# feedline.net
KiCad netlist of a schematic drawn in EAGLE
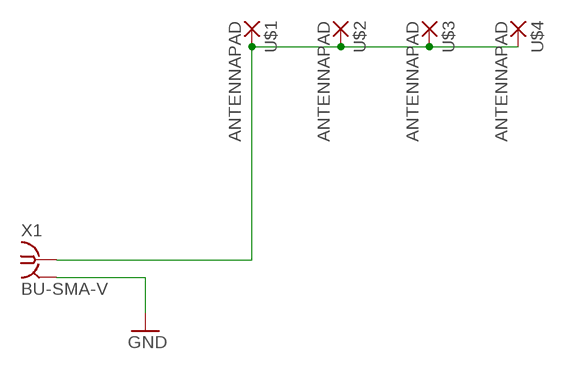
[diagram p0: schematic, sheet 1]

(export (version "E")
  (design (tool "Eeschema 10.0.6"))
  (components
    (comp (ref "U$1")
      (value "ANTENNAPAD")
      (footprint "eagle-import:CMMOUNTPAD")
      (libsource (lib "eagle-import") (part "ANTENNAPAD"))
    )
    (comp (ref "U$2")
      (value "ANTENNAPAD")
      (footprint "eagle-import:CMMOUNTPAD")
      (libsource (lib "eagle-import") (part "ANTENNAPAD"))
    )
    (comp (ref "U$3")
      (value "ANTENNAPAD")
      (footprint "eagle-import:CMMOUNTPAD")
      (libsource (lib "eagle-import") (part "ANTENNAPAD"))
    )
    (comp (ref "U$4")
      (value "ANTENNAPAD")
      (footprint "eagle-import:CMMOUNTPAD")
      (libsource (lib "eagle-import") (part "ANTENNAPAD"))
    )
    (comp (ref "X1")
      (value "BU-SMA-V")
      (footprint "eagle-import:BU-SMA-V")
      (libsource (lib "eagle-import") (part "BU-SMA-V"))
    )
  )
  (nets
    (net (code "1") (name "GND") (class "Default")
      (node (ref "X1") (pin "2") (pinfunction "2_2") (pintype "passive"))
      (node (ref "X1") (pin "3") (pinfunction "2_3") (pintype "passive"))
      (node (ref "X1") (pin "4") (pinfunction "2_4") (pintype "passive"))
      (node (ref "X1") (pin "5") (pinfunction "2_5") (pintype "passive"))
    )
    (net (code "2") (name "Net-(U$1-P)") (class "Default")
      (node (ref "U$1") (pin "P$1") (pinfunction "P_P$1") (pintype "passive"))
      (node (ref "U$2") (pin "P$1") (pinfunction "P_P$1") (pintype "passive"))
      (node (ref "U$3") (pin "P$1") (pinfunction "P_P$1") (pintype "passive"))
      (node (ref "U$4") (pin "P$1") (pinfunction "P_P$1") (pintype "passive"))
      (node (ref "X1") (pin "1") (pinfunction "1_1") (pintype "passive"))
    )
  )
)
